# basisplatine.net
KiCad netlist of a schematic drawn in EAGLE
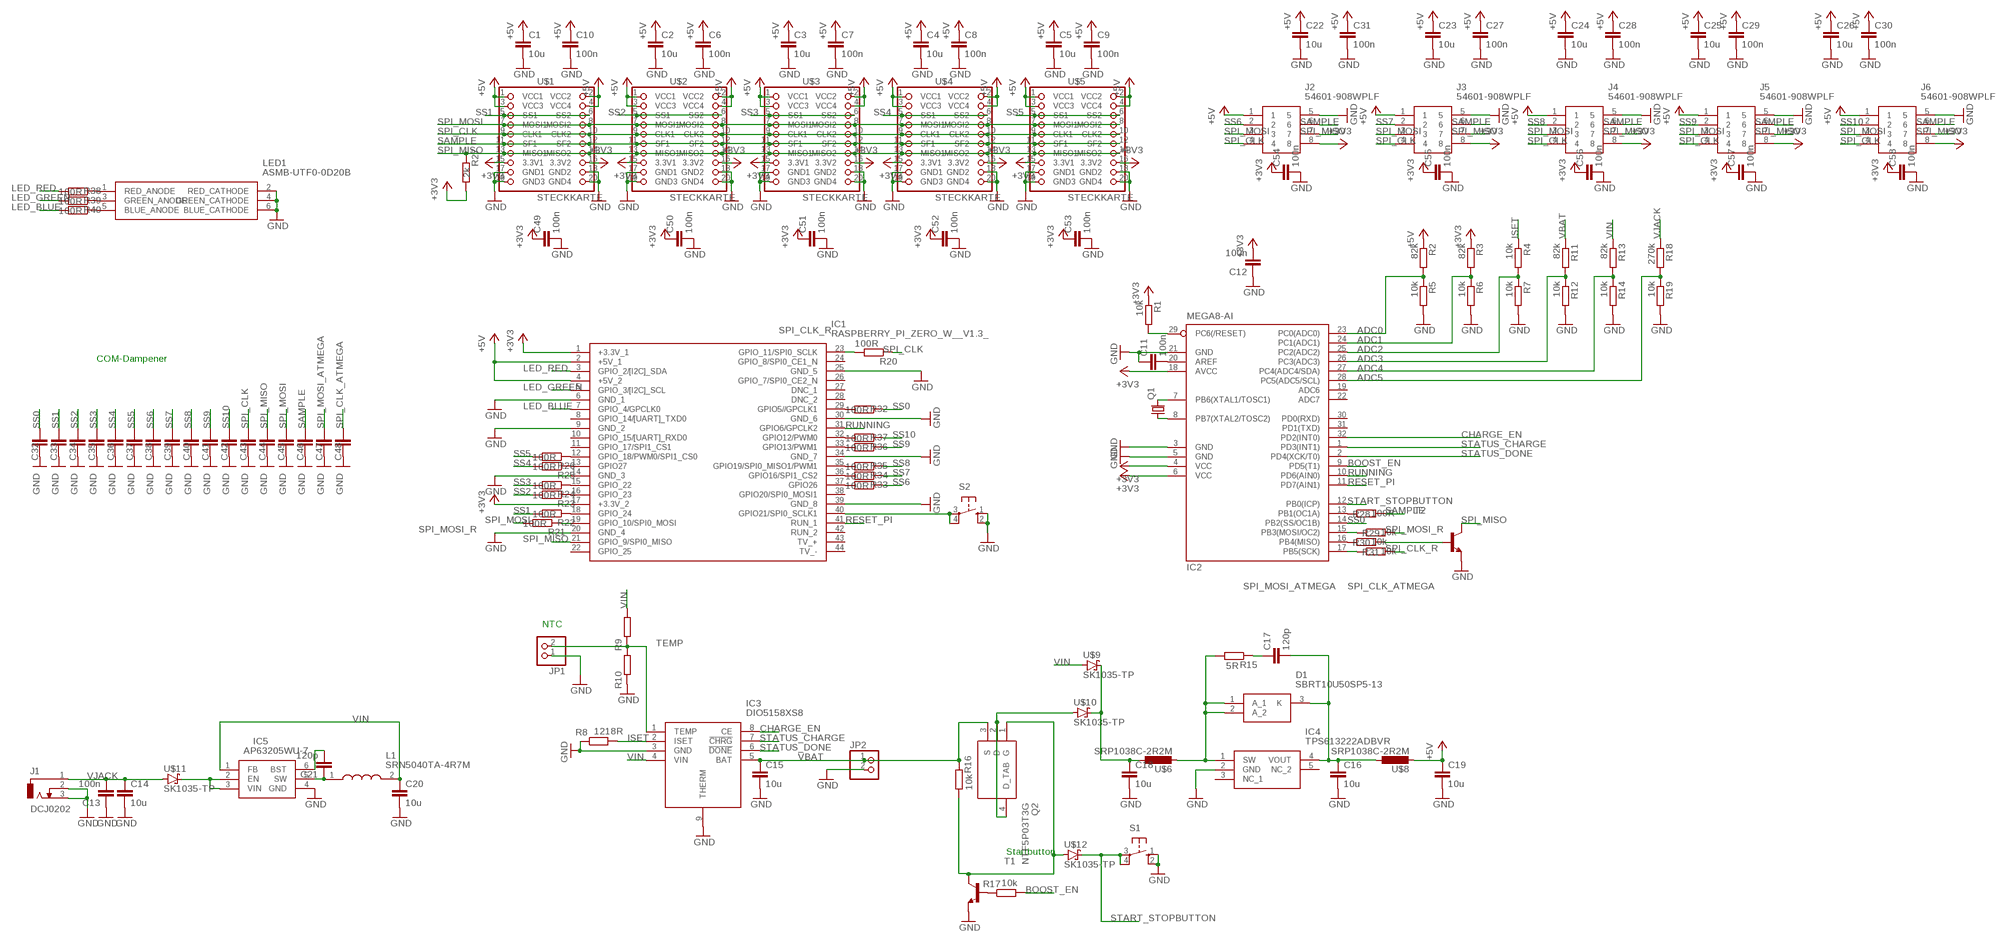
[diagram p0: schematic, sheet 1]

(export (version "E")
  (design (tool "Eeschema 10.0.6"))
  (components
    (comp (ref "C1")
      (value "10u")
      (footprint "eagle-import:C1206")
      (libsource (lib "eagle-import") (part "C-EUC1206"))
    )
    (comp (ref "C2")
      (value "10u")
      (footprint "eagle-import:C1206K")
      (libsource (lib "eagle-import") (part "C-EUC1206K"))
    )
    (comp (ref "C3")
      (value "10u")
      (footprint "eagle-import:C1206K")
      (libsource (lib "eagle-import") (part "C-EUC1206K"))
    )
    (comp (ref "C4")
      (value "10u")
      (footprint "eagle-import:C1206K")
      (libsource (lib "eagle-import") (part "C-EUC1206K"))
    )
    (comp (ref "C5")
      (value "10u")
      (footprint "eagle-import:C1206K")
      (libsource (lib "eagle-import") (part "C-EUC1206K"))
    )
    (comp (ref "C6")
      (value "100n")
      (footprint "eagle-import:C0603K")
      (libsource (lib "eagle-import") (part "C-EUC0603K"))
    )
    (comp (ref "C7")
      (value "100n")
      (footprint "eagle-import:C0603K")
      (libsource (lib "eagle-import") (part "C-EUC0603K"))
    )
    (comp (ref "C8")
      (value "100n")
      (footprint "eagle-import:C0603K")
      (libsource (lib "eagle-import") (part "C-EUC0603K"))
    )
    (comp (ref "C9")
      (value "100n")
      (footprint "eagle-import:C0603K")
      (libsource (lib "eagle-import") (part "C-EUC0603K"))
    )
    (comp (ref "C10")
      (value "100n")
      (footprint "eagle-import:C0603K")
      (libsource (lib "eagle-import") (part "C-EUC0603K"))
    )
    (comp (ref "C11")
      (value "100n")
      (footprint "eagle-import:C0603K")
      (libsource (lib "eagle-import") (part "C-EUC0603K"))
    )
    (comp (ref "C12")
      (value "100n")
      (footprint "eagle-import:C0603K")
      (libsource (lib "eagle-import") (part "C-EUC0603K"))
    )
    (comp (ref "C13")
      (value "100n")
      (footprint "eagle-import:C0603K")
      (libsource (lib "eagle-import") (part "C-EUC0603K"))
    )
    (comp (ref "C14")
      (value "10u")
      (footprint "eagle-import:C1206K")
      (libsource (lib "eagle-import") (part "C-EUC1206K"))
    )
    (comp (ref "C15")
      (value "10u")
      (footprint "eagle-import:C1206K")
      (libsource (lib "eagle-import") (part "C-EUC1206K"))
    )
    (comp (ref "C16")
      (value "10u")
      (footprint "eagle-import:C1206K")
      (libsource (lib "eagle-import") (part "C-EUC1206K"))
    )
    (comp (ref "C17")
      (value "120p")
      (footprint "eagle-import:C0603K")
      (libsource (lib "eagle-import") (part "C-EUC0603K"))
    )
    (comp (ref "C18")
      (value "10u")
      (footprint "eagle-import:C1206K")
      (libsource (lib "eagle-import") (part "C-EUC1206K"))
    )
    (comp (ref "C19")
      (value "10u")
      (footprint "eagle-import:C1206K")
      (libsource (lib "eagle-import") (part "C-EUC1206K"))
    )
    (comp (ref "C20")
      (value "10u")
      (footprint "eagle-import:C1206K")
      (libsource (lib "eagle-import") (part "C-EUC1206K"))
    )
    (comp (ref "C21")
      (value "120p")
      (footprint "eagle-import:C0603K")
      (libsource (lib "eagle-import") (part "C-EUC0603K"))
    )
    (comp (ref "C22")
      (value "10u")
      (footprint "eagle-import:C1206")
      (libsource (lib "eagle-import") (part "C-EUC1206"))
    )
    (comp (ref "C23")
      (value "10u")
      (footprint "eagle-import:C1206K")
      (libsource (lib "eagle-import") (part "C-EUC1206K"))
    )
    (comp (ref "C24")
      (value "10u")
      (footprint "eagle-import:C1206K")
      (libsource (lib "eagle-import") (part "C-EUC1206K"))
    )
    (comp (ref "C25")
      (value "10u")
      (footprint "eagle-import:C1206K")
      (libsource (lib "eagle-import") (part "C-EUC1206K"))
    )
    (comp (ref "C26")
      (value "10u")
      (footprint "eagle-import:C1206K")
      (libsource (lib "eagle-import") (part "C-EUC1206K"))
    )
    (comp (ref "C27")
      (value "100n")
      (footprint "eagle-import:C0603K")
      (libsource (lib "eagle-import") (part "C-EUC0603K"))
    )
    (comp (ref "C28")
      (value "100n")
      (footprint "eagle-import:C0603K")
      (libsource (lib "eagle-import") (part "C-EUC0603K"))
    )
    (comp (ref "C29")
      (value "100n")
      (footprint "eagle-import:C0603K")
      (libsource (lib "eagle-import") (part "C-EUC0603K"))
    )
    (comp (ref "C30")
      (value "100n")
      (footprint "eagle-import:C0603K")
      (libsource (lib "eagle-import") (part "C-EUC0603K"))
    )
    (comp (ref "C31")
      (value "100n")
      (footprint "eagle-import:C0603K")
      (libsource (lib "eagle-import") (part "C-EUC0603K"))
    )
    (comp (ref "C32")
      (value "C-EUC0603K")
      (footprint "eagle-import:C0603K")
      (libsource (lib "eagle-import") (part "C-EUC0603K"))
    )
    (comp (ref "C33")
      (value "C-EUC0603K")
      (footprint "eagle-import:C0603K")
      (libsource (lib "eagle-import") (part "C-EUC0603K"))
    )
    (comp (ref "C34")
      (value "C-EUC0603K")
      (footprint "eagle-import:C0603K")
      (libsource (lib "eagle-import") (part "C-EUC0603K"))
    )
    (comp (ref "C35")
      (value "C-EUC0603K")
      (footprint "eagle-import:C0603K")
      (libsource (lib "eagle-import") (part "C-EUC0603K"))
    )
    (comp (ref "C36")
      (value "C-EUC0603K")
      (footprint "eagle-import:C0603K")
      (libsource (lib "eagle-import") (part "C-EUC0603K"))
    )
    (comp (ref "C37")
      (value "C-EUC0603K")
      (footprint "eagle-import:C0603K")
      (libsource (lib "eagle-import") (part "C-EUC0603K"))
    )
    (comp (ref "C38")
      (value "C-EUC0603K")
      (footprint "eagle-import:C0603K")
      (libsource (lib "eagle-import") (part "C-EUC0603K"))
    )
    (comp (ref "C39")
      (value "C-EUC0603K")
      (footprint "eagle-import:C0603K")
      (libsource (lib "eagle-import") (part "C-EUC0603K"))
    )
    (comp (ref "C40")
      (value "C-EUC0603K")
      (footprint "eagle-import:C0603K")
      (libsource (lib "eagle-import") (part "C-EUC0603K"))
    )
    (comp (ref "C41")
      (value "C-EUC0603K")
      (footprint "eagle-import:C0603K")
      (libsource (lib "eagle-import") (part "C-EUC0603K"))
    )
    (comp (ref "C42")
      (value "C-EUC0603K")
      (footprint "eagle-import:C0603K")
      (libsource (lib "eagle-import") (part "C-EUC0603K"))
    )
    (comp (ref "C43")
      (value "C-EUC0603K")
      (footprint "eagle-import:C0603K")
      (libsource (lib "eagle-import") (part "C-EUC0603K"))
    )
    (comp (ref "C44")
      (value "C-EUC0603K")
      (footprint "eagle-import:C0603K")
      (libsource (lib "eagle-import") (part "C-EUC0603K"))
    )
    (comp (ref "C45")
      (value "C-EUC0603K")
      (footprint "eagle-import:C0603K")
      (libsource (lib "eagle-import") (part "C-EUC0603K"))
    )
    (comp (ref "C46")
      (value "C-EUC0603K")
      (footprint "eagle-import:C0603K")
      (libsource (lib "eagle-import") (part "C-EUC0603K"))
    )
    (comp (ref "C47")
      (value "C-EUC0603K")
      (footprint "eagle-import:C0603K")
      (libsource (lib "eagle-import") (part "C-EUC0603K"))
    )
    (comp (ref "C48")
      (value "C-EUC0603K")
      (footprint "eagle-import:C0603K")
      (libsource (lib "eagle-import") (part "C-EUC0603K"))
    )
    (comp (ref "C49")
      (value "100n")
      (footprint "eagle-import:C0603K")
      (libsource (lib "eagle-import") (part "C-EUC0603K"))
    )
    (comp (ref "C50")
      (value "100n")
      (footprint "eagle-import:C0603K")
      (libsource (lib "eagle-import") (part "C-EUC0603K"))
    )
    (comp (ref "C51")
      (value "100n")
      (footprint "eagle-import:C0603K")
      (libsource (lib "eagle-import") (part "C-EUC0603K"))
    )
    (comp (ref "C52")
      (value "100n")
      (footprint "eagle-import:C0603K")
      (libsource (lib "eagle-import") (part "C-EUC0603K"))
    )
    (comp (ref "C53")
      (value "100n")
      (footprint "eagle-import:C0603K")
      (libsource (lib "eagle-import") (part "C-EUC0603K"))
    )
    (comp (ref "C54")
      (value "100n")
      (footprint "eagle-import:C0603K")
      (libsource (lib "eagle-import") (part "C-EUC0603K"))
    )
    (comp (ref "C55")
      (value "100n")
      (footprint "eagle-import:C0603K")
      (libsource (lib "eagle-import") (part "C-EUC0603K"))
    )
    (comp (ref "C56")
      (value "100n")
      (footprint "eagle-import:C0603K")
      (libsource (lib "eagle-import") (part "C-EUC0603K"))
    )
    (comp (ref "C57")
      (value "100n")
      (footprint "eagle-import:C0603K")
      (libsource (lib "eagle-import") (part "C-EUC0603K"))
    )
    (comp (ref "C58")
      (value "100n")
      (footprint "eagle-import:C0603K")
      (libsource (lib "eagle-import") (part "C-EUC0603K"))
    )
    (comp (ref "D1")
      (value "SBRT10U50SP5-13")
      (footprint "eagle-import:SBRT10U50SP513")
      (fields (field (name "MOUSER_PART_NUMBER") "621-SBRT10U50SP5-13"))
      (libsource (lib "eagle-import") (part "SBRT10U50SP5-13"))
    )
    (comp (ref "IC1")
      (value "RASPBERRY_PI_ZERO_W__V1.3_")
      (footprint "eagle-import:RASPBERRYPIZEROWV13")
      (fields (field (name "MANUFACTURER_PART_NUMBER") "Raspberry Pi Zero W (v1.3)"))
      (libsource (lib "eagle-import") (part "RASPBERRY_PI_ZERO_W__V1.3_"))
    )
    (comp (ref "IC2")
      (value "MEGA8-AI")
      (footprint "eagle-import:TQFP32-08")
      (fields (field (name "MPN") "ATMEGA8-16AU"))
      (libsource (lib "eagle-import") (part "MEGA8-AI"))
    )
    (comp (ref "IC3")
      (value "DIO5158XS8")
      (footprint "eagle-import:SOIC127P600X170-9N")
      (fields (field (name "MOUSER_PART_NUMBER") "453-DIO5158XS8"))
      (libsource (lib "eagle-import") (part "DIO5158XS8"))
    )
    (comp (ref "IC4")
      (value "TPS613222ADBVR")
      (footprint "eagle-import:SOT95P280X145-5N")
      (fields (field (name "MOUSER_PART_NUMBER") "595-TPS613222ADBVR"))
      (libsource (lib "eagle-import") (part "TPS613222ADBVR"))
    )
    (comp (ref "IC5")
      (value "AP63205WU-7")
      (footprint "eagle-import:SOT95P280X100-6N")
      (fields (field (name "MOUSER_PART_NUMBER") "621-AP63205WU-7"))
      (libsource (lib "eagle-import") (part "AP63205WU-7"))
    )
    (comp (ref "J1")
      (value "DCJ0202")
      (footprint "eagle-import:DCJ0202")
      (libsource (lib "eagle-import") (part "DCJ0202"))
    )
    (comp (ref "J2")
      (value "54601-908WPLF")
      (footprint "eagle-import:54601908WPLF")
      (fields (field (name "MOUSER_PART_NUMBER") "649-54601-908WPLF"))
      (libsource (lib "eagle-import") (part "54601-908WPLF"))
    )
    (comp (ref "J3")
      (value "54601-908WPLF")
      (footprint "eagle-import:54601908WPLF")
      (fields (field (name "MOUSER_PART_NUMBER") "649-54601-908WPLF"))
      (libsource (lib "eagle-import") (part "54601-908WPLF"))
    )
    (comp (ref "J4")
      (value "54601-908WPLF")
      (footprint "eagle-import:54601908WPLF")
      (fields (field (name "MOUSER_PART_NUMBER") "649-54601-908WPLF"))
      (libsource (lib "eagle-import") (part "54601-908WPLF"))
    )
    (comp (ref "J5")
      (value "54601-908WPLF")
      (footprint "eagle-import:54601908WPLF")
      (fields (field (name "MOUSER_PART_NUMBER") "649-54601-908WPLF"))
      (libsource (lib "eagle-import") (part "54601-908WPLF"))
    )
    (comp (ref "J6")
      (value "54601-908WPLF")
      (footprint "eagle-import:54601908WPLF")
      (fields (field (name "MOUSER_PART_NUMBER") "649-54601-908WPLF"))
      (libsource (lib "eagle-import") (part "54601-908WPLF"))
    )
    (comp (ref "JP1")
      (value "PINHD-1X2")
      (footprint "eagle-import:1X02")
      (libsource (lib "eagle-import") (part "PINHD-1X2"))
    )
    (comp (ref "JP2")
      (value "PINHD-1X2")
      (footprint "eagle-import:1X02")
      (libsource (lib "eagle-import") (part "PINHD-1X2"))
    )
    (comp (ref "L1")
      (value "SRN5040TA-4R7M")
      (footprint "eagle-import:SRN5040TA4R7M")
      (fields (field (name "MOUSER_PART_NUMBER") "652-SRN5040TA-4R7M"))
      (libsource (lib "eagle-import") (part "SRN5040TA-4R7M"))
    )
    (comp (ref "LED1")
      (value "ASMB-UTF0-0D20B")
      (footprint "eagle-import:ASMBUTF00D20B")
      (fields (field (name "MOUSER_PART_NUMBER") "630-ASMB-UTF0-0D20B"))
      (libsource (lib "eagle-import") (part "ASMB-UTF0-0D20B"))
    )
    (comp (ref "Q1")
      (value "CRYSTALTC38H")
      (footprint "eagle-import:TC38H")
      (libsource (lib "eagle-import") (part "CRYSTALTC38H"))
    )
    (comp (ref "Q2")
      (value "NTF5P03T3G")
      (footprint "eagle-import:SOT230P700X175-4N")
      (fields (field (name "MOUSER_PART_NUMBER") "863-NTF5P03T3G"))
      (libsource (lib "eagle-import") (part "NTF5P03T3G"))
    )
    (comp (ref "R1")
      (value "10k")
      (footprint "eagle-import:R0603")
      (libsource (lib "eagle-import") (part "R-EU_R0603"))
    )
    (comp (ref "R2")
      (value "82k")
      (footprint "eagle-import:R0603")
      (libsource (lib "eagle-import") (part "R-EU_R0603"))
    )
    (comp (ref "R3")
      (value "82k")
      (footprint "eagle-import:R0603")
      (libsource (lib "eagle-import") (part "R-EU_R0603"))
    )
    (comp (ref "R4")
      (value "10k")
      (footprint "eagle-import:R0603")
      (libsource (lib "eagle-import") (part "R-EU_R0603"))
    )
    (comp (ref "R5")
      (value "10k")
      (footprint "eagle-import:R0603")
      (libsource (lib "eagle-import") (part "R-EU_R0603"))
    )
    (comp (ref "R6")
      (value "10k")
      (footprint "eagle-import:R0603")
      (libsource (lib "eagle-import") (part "R-EU_R0603"))
    )
    (comp (ref "R7")
      (value "10k")
      (footprint "eagle-import:R0603")
      (libsource (lib "eagle-import") (part "R-EU_R0603"))
    )
    (comp (ref "R8")
      (value "1218R")
      (footprint "eagle-import:R0603")
      (libsource (lib "eagle-import") (part "R-EU_R0603"))
    )
    (comp (ref "R9")
      (value "R-EU_R0603")
      (footprint "eagle-import:R0603")
      (libsource (lib "eagle-import") (part "R-EU_R0603"))
    )
    (comp (ref "R10")
      (value "R-EU_R0603")
      (footprint "eagle-import:R0603")
      (libsource (lib "eagle-import") (part "R-EU_R0603"))
    )
    (comp (ref "R11")
      (value "82k")
      (footprint "eagle-import:R0603")
      (libsource (lib "eagle-import") (part "R-EU_R0603"))
    )
    (comp (ref "R12")
      (value "10k")
      (footprint "eagle-import:R0603")
      (libsource (lib "eagle-import") (part "R-EU_R0603"))
    )
    (comp (ref "R13")
      (value "82k")
      (footprint "eagle-import:R0603")
      (libsource (lib "eagle-import") (part "R-EU_R0603"))
    )
    (comp (ref "R14")
      (value "10k")
      (footprint "eagle-import:R0603")
      (libsource (lib "eagle-import") (part "R-EU_R0603"))
    )
    (comp (ref "R15")
      (value "5R")
      (footprint "eagle-import:R0603")
      (libsource (lib "eagle-import") (part "R-EU_R0603"))
    )
    (comp (ref "R16")
      (value "10k")
      (footprint "eagle-import:R0603")
      (libsource (lib "eagle-import") (part "R-EU_R0603"))
    )
    (comp (ref "R17")
      (value "10k")
      (footprint "eagle-import:R0603")
      (libsource (lib "eagle-import") (part "R-EU_R0603"))
    )
    (comp (ref "R18")
      (value "270k")
      (footprint "eagle-import:R0603")
      (libsource (lib "eagle-import") (part "R-EU_R0603"))
    )
    (comp (ref "R19")
      (value "10k")
      (footprint "eagle-import:R0603")
      (libsource (lib "eagle-import") (part "R-EU_R0603"))
    )
    (comp (ref "R20")
      (value "100R")
      (footprint "eagle-import:R0603")
      (libsource (lib "eagle-import") (part "R-EU_R0603"))
    )
    (comp (ref "R21")
      (value "100R")
      (footprint "eagle-import:R0603")
      (libsource (lib "eagle-import") (part "R-EU_R0603"))
    )
    (comp (ref "R22")
      (value "100R")
      (footprint "eagle-import:R0603")
      (libsource (lib "eagle-import") (part "R-EU_R0603"))
    )
    (comp (ref "R23")
      (value "100R")
      (footprint "eagle-import:R0603")
      (libsource (lib "eagle-import") (part "R-EU_R0603"))
    )
    (comp (ref "R24")
      (value "100R")
      (footprint "eagle-import:R0603")
      (libsource (lib "eagle-import") (part "R-EU_R0603"))
    )
    (comp (ref "R25")
      (value "100R")
      (footprint "eagle-import:R0603")
      (libsource (lib "eagle-import") (part "R-EU_R0603"))
    )
    (comp (ref "R26")
      (value "100R")
      (footprint "eagle-import:R0603")
      (libsource (lib "eagle-import") (part "R-EU_R0603"))
    )
    (comp (ref "R27")
      (value "2k")
      (footprint "eagle-import:R0603")
      (libsource (lib "eagle-import") (part "R-EU_R0603"))
    )
    (comp (ref "R28")
      (value "100R")
      (footprint "eagle-import:R0603")
      (libsource (lib "eagle-import") (part "R-EU_R0603"))
    )
    (comp (ref "R29")
      (value "10k")
      (footprint "eagle-import:R0603")
      (libsource (lib "eagle-import") (part "R-EU_R0603"))
    )
    (comp (ref "R30")
      (value "10k")
      (footprint "eagle-import:R0603")
      (libsource (lib "eagle-import") (part "R-EU_R0603"))
    )
    (comp (ref "R31")
      (value "10k")
      (footprint "eagle-import:R0603")
      (libsource (lib "eagle-import") (part "R-EU_R0603"))
    )
    (comp (ref "R32")
      (value "100R")
      (footprint "eagle-import:R0603")
      (libsource (lib "eagle-import") (part "R-EU_R0603"))
    )
    (comp (ref "R33")
      (value "100R")
      (footprint "eagle-import:R0603")
      (libsource (lib "eagle-import") (part "R-EU_R0603"))
    )
    (comp (ref "R34")
      (value "100R")
      (footprint "eagle-import:R0603")
      (libsource (lib "eagle-import") (part "R-EU_R0603"))
    )
    (comp (ref "R35")
      (value "100R")
      (footprint "eagle-import:R0603")
      (libsource (lib "eagle-import") (part "R-EU_R0603"))
    )
    (comp (ref "R36")
      (value "100R")
      (footprint "eagle-import:R0603")
      (libsource (lib "eagle-import") (part "R-EU_R0603"))
    )
    (comp (ref "R37")
      (value "100R")
      (footprint "eagle-import:R0603")
      (libsource (lib "eagle-import") (part "R-EU_R0603"))
    )
    (comp (ref "R38")
      (value "100R")
      (footprint "eagle-import:R0603")
      (libsource (lib "eagle-import") (part "R-EU_R0603"))
    )
    (comp (ref "R39")
      (value "100R")
      (footprint "eagle-import:R0603")
      (libsource (lib "eagle-import") (part "R-EU_R0603"))
    )
    (comp (ref "R40")
      (value "100R")
      (footprint "eagle-import:R0603")
      (libsource (lib "eagle-import") (part "R-EU_R0603"))
    )
    (comp (ref "S1")
      (value "10-XX")
      (footprint "eagle-import:B3F-10XX")
      (fields (field (name "MPN") "B3F-1000"))
      (libsource (lib "eagle-import") (part "10-XX"))
    )
    (comp (ref "S2")
      (value "10-XX")
      (footprint "eagle-import:B3F-10XX")
      (fields (field (name "MPN") "B3F-1000"))
      (libsource (lib "eagle-import") (part "10-XX"))
    )
    (comp (ref "T1")
      (value "BC808-NPN-SOT23-BEC")
      (footprint "eagle-import:SOT23-BEC")
      (libsource (lib "eagle-import") (part "-NPN-SOT23-BECBC808"))
    )
    (comp (ref "T2")
      (value "BC808-NPN-SOT23-BEC")
      (footprint "eagle-import:SOT23-BEC")
      (libsource (lib "eagle-import") (part "-NPN-SOT23-BECBC808"))
    )
    (comp (ref "U$1")
      (value "STECKKARTE")
      (footprint "eagle-import:2X10")
      (libsource (lib "eagle-import") (part "STECKKARTE"))
    )
    (comp (ref "U$2")
      (value "STECKKARTE")
      (footprint "eagle-import:2X10")
      (libsource (lib "eagle-import") (part "STECKKARTE"))
    )
    (comp (ref "U$3")
      (value "STECKKARTE")
      (footprint "eagle-import:2X10")
      (libsource (lib "eagle-import") (part "STECKKARTE"))
    )
    (comp (ref "U$4")
      (value "STECKKARTE")
      (footprint "eagle-import:2X10")
      (libsource (lib "eagle-import") (part "STECKKARTE"))
    )
    (comp (ref "U$5")
      (value "STECKKARTE")
      (footprint "eagle-import:2X10")
      (libsource (lib "eagle-import") (part "STECKKARTE"))
    )
    (comp (ref "U$6")
      (value "SRP1038C-2R2M")
      (footprint "eagle-import:SRP1038C-2R2M")
      (libsource (lib "eagle-import") (part "SRP1038C-2R2M"))
    )
    (comp (ref "U$8")
      (value "SRP1038C-2R2M")
      (footprint "eagle-import:SRP1038C-2R2M")
      (libsource (lib "eagle-import") (part "SRP1038C-2R2M"))
    )
    (comp (ref "U$9")
      (value "SK1035-TP")
      (footprint "eagle-import:INDC2520X120N")
      (libsource (lib "eagle-import") (part "SK1035-TP"))
    )
    (comp (ref "U$10")
      (value "SK1035-TP")
      (footprint "eagle-import:INDC2520X120N")
      (libsource (lib "eagle-import") (part "SK1035-TP"))
    )
    (comp (ref "U$11")
      (value "SK1035-TP")
      (footprint "eagle-import:INDC2520X120N")
      (libsource (lib "eagle-import") (part "SK1035-TP"))
    )
    (comp (ref "U$12")
      (value "SK1035-TP")
      (footprint "eagle-import:INDC2520X120N")
      (libsource (lib "eagle-import") (part "SK1035-TP"))
    )
  )
  (nets
    (net (code "1") (name "+3V3") (class "Default")
      (node (ref "C12") (pin "2") (pinfunction "2_2") (pintype "passive"))
      (node (ref "C49") (pin "1") (pinfunction "1_1") (pintype "passive"))
      (node (ref "C50") (pin "1") (pinfunction "1_1") (pintype "passive"))
      (node (ref "C51") (pin "1") (pinfunction "1_1") (pintype "passive"))
      (node (ref "C52") (pin "1") (pinfunction "1_1") (pintype "passive"))
      (node (ref "C53") (pin "1") (pinfunction "1_1") (pintype "passive"))
      (node (ref "C54") (pin "1") (pinfunction "1_1") (pintype "passive"))
      (node (ref "C55") (pin "1") (pinfunction "1_1") (pintype "passive"))
      (node (ref "C56") (pin "1") (pinfunction "1_1") (pintype "passive"))
      (node (ref "C57") (pin "1") (pinfunction "1_1") (pintype "passive"))
      (node (ref "C58") (pin "1") (pinfunction "1_1") (pintype "passive"))
      (node (ref "IC1") (pin "1") (pinfunction "+3.3V_1_1") (pintype "bidirectional"))
      (node (ref "IC1") (pin "17") (pinfunction "+3.3V_2_17") (pintype "bidirectional"))
      (node (ref "IC2") (pin "18") (pinfunction "AVCC_18") (pintype "power_in"))
      (node (ref "IC2") (pin "4") (pinfunction "VCC_4") (pintype "power_in"))
      (node (ref "IC2") (pin "6") (pinfunction "VCC_6") (pintype "power_in"))
      (node (ref "J2") (pin "8") (pinfunction "8_8") (pintype "bidirectional"))
      (node (ref "J3") (pin "8") (pinfunction "8_8") (pintype "bidirectional"))
      (node (ref "J4") (pin "8") (pinfunction "8_8") (pintype "bidirectional"))
      (node (ref "J5") (pin "8") (pinfunction "8_8") (pintype "bidirectional"))
      (node (ref "J6") (pin "8") (pinfunction "8_8") (pintype "bidirectional"))
      (node (ref "R1") (pin "1") (pinfunction "1_1") (pintype "passive"))
      (node (ref "R27") (pin "2") (pinfunction "2_2") (pintype "passive"))
      (node (ref "R3") (pin "1") (pinfunction "1_1") (pintype "passive"))
      (node (ref "U$1") (pin "15") (pinfunction "3.3V1_15") (pintype "power_in"))
      (node (ref "U$1") (pin "16") (pinfunction "3.3V2_16") (pintype "power_in"))
      (node (ref "U$2") (pin "15") (pinfunction "3.3V1_15") (pintype "power_in"))
      (node (ref "U$2") (pin "16") (pinfunction "3.3V2_16") (pintype "power_in"))
      (node (ref "U$3") (pin "15") (pinfunction "3.3V1_15") (pintype "power_in"))
      (node (ref "U$3") (pin "16") (pinfunction "3.3V2_16") (pintype "power_in"))
      (node (ref "U$4") (pin "15") (pinfunction "3.3V1_15") (pintype "power_in"))
      (node (ref "U$4") (pin "16") (pinfunction "3.3V2_16") (pintype "power_in"))
      (node (ref "U$5") (pin "15") (pinfunction "3.3V1_15") (pintype "power_in"))
      (node (ref "U$5") (pin "16") (pinfunction "3.3V2_16") (pintype "power_in"))
    )
    (net (code "2") (name "+5V") (class "Default")
      (node (ref "C1") (pin "1") (pinfunction "1_1") (pintype "passive"))
      (node (ref "C10") (pin "1") (pinfunction "1_1") (pintype "passive"))
      (node (ref "C19") (pin "1") (pinfunction "1_1") (pintype "passive"))
      (node (ref "C2") (pin "1") (pinfunction "1_1") (pintype "passive"))
      (node (ref "C22") (pin "1") (pinfunction "1_1") (pintype "passive"))
      (node (ref "C23") (pin "1") (pinfunction "1_1") (pintype "passive"))
      (node (ref "C24") (pin "1") (pinfunction "1_1") (pintype "passive"))
      (node (ref "C25") (pin "1") (pinfunction "1_1") (pintype "passive"))
      (node (ref "C26") (pin "1") (pinfunction "1_1") (pintype "passive"))
      (node (ref "C27") (pin "1") (pinfunction "1_1") (pintype "passive"))
      (node (ref "C28") (pin "1") (pinfunction "1_1") (pintype "passive"))
      (node (ref "C29") (pin "1") (pinfunction "1_1") (pintype "passive"))
      (node (ref "C3") (pin "1") (pinfunction "1_1") (pintype "passive"))
      (node (ref "C30") (pin "1") (pinfunction "1_1") (pintype "passive"))
      (node (ref "C31") (pin "1") (pinfunction "1_1") (pintype "passive"))
      (node (ref "C4") (pin "1") (pinfunction "1_1") (pintype "passive"))
      (node (ref "C5") (pin "1") (pinfunction "1_1") (pintype "passive"))
      (node (ref "C6") (pin "1") (pinfunction "1_1") (pintype "passive"))
      (node (ref "C7") (pin "1") (pinfunction "1_1") (pintype "passive"))
      (node (ref "C8") (pin "1") (pinfunction "1_1") (pintype "passive"))
      (node (ref "C9") (pin "1") (pinfunction "1_1") (pintype "passive"))
      (node (ref "IC1") (pin "2") (pinfunction "+5V_1_2") (pintype "bidirectional"))
      (node (ref "IC1") (pin "4") (pinfunction "+5V_2_4") (pintype "bidirectional"))
      (node (ref "J2") (pin "1") (pinfunction "1_1") (pintype "bidirectional"))
      (node (ref "J3") (pin "1") (pinfunction "1_1") (pintype "bidirectional"))
      (node (ref "J4") (pin "1") (pinfunction "1_1") (pintype "bidirectional"))
      (node (ref "J5") (pin "1") (pinfunction "1_1") (pintype "bidirectional"))
      (node (ref "J6") (pin "1") (pinfunction "1_1") (pintype "bidirectional"))
      (node (ref "R2") (pin "1") (pinfunction "1_1") (pintype "passive"))
      (node (ref "U$1") (pin "1") (pinfunction "VCC1_1") (pintype "power_in"))
      (node (ref "U$1") (pin "2") (pinfunction "VCC2_2") (pintype "power_in"))
      (node (ref "U$1") (pin "3") (pinfunction "VCC3_3") (pintype "power_in"))
      (node (ref "U$1") (pin "4") (pinfunction "VCC4_4") (pintype "power_in"))
      (node (ref "U$2") (pin "1") (pinfunction "VCC1_1") (pintype "power_in"))
      (node (ref "U$2") (pin "2") (pinfunction "VCC2_2") (pintype "power_in"))
      (node (ref "U$2") (pin "3") (pinfunction "VCC3_3") (pintype "power_in"))
      (node (ref "U$2") (pin "4") (pinfunction "VCC4_4") (pintype "power_in"))
      (node (ref "U$3") (pin "1") (pinfunction "VCC1_1") (pintype "power_in"))
      (node (ref "U$3") (pin "2") (pinfunction "VCC2_2") (pintype "power_in"))
      (node (ref "U$3") (pin "3") (pinfunction "VCC3_3") (pintype "power_in"))
      (node (ref "U$3") (pin "4") (pinfunction "VCC4_4") (pintype "power_in"))
      (node (ref "U$4") (pin "1") (pinfunction "VCC1_1") (pintype "power_in"))
      (node (ref "U$4") (pin "2") (pinfunction "VCC2_2") (pintype "power_in"))
      (node (ref "U$4") (pin "3") (pinfunction "VCC3_3") (pintype "power_in"))
      (node (ref "U$4") (pin "4") (pinfunction "VCC4_4") (pintype "power_in"))
      (node (ref "U$5") (pin "1") (pinfunction "VCC1_1") (pintype "power_in"))
      (node (ref "U$5") (pin "2") (pinfunction "VCC2_2") (pintype "power_in"))
      (node (ref "U$5") (pin "3") (pinfunction "VCC3_3") (pintype "power_in"))
      (node (ref "U$5") (pin "4") (pinfunction "VCC4_4") (pintype "power_in"))
      (node (ref "U$8") (pin "P$2") (pinfunction "2_P$2") (pintype "passive"))
    )
    (net (code "3") (name "/ADC0") (class "Default")
      (node (ref "IC2") (pin "23") (pinfunction "PC0(ADC0)_23") (pintype "bidirectional"))
      (node (ref "R2") (pin "2") (pinfunction "2_2") (pintype "passive"))
      (node (ref "R5") (pin "1") (pinfunction "1_1") (pintype "passive"))
    )
    (net (code "4") (name "/ADC1") (class "Default")
      (node (ref "IC2") (pin "24") (pinfunction "PC1(ADC1)_24") (pintype "bidirectional"))
      (node (ref "R3") (pin "2") (pinfunction "2_2") (pintype "passive"))
      (node (ref "R6") (pin "1") (pinfunction "1_1") (pintype "passive"))
    )
    (net (code "5") (name "/ADC2") (class "Default")
      (node (ref "IC2") (pin "25") (pinfunction "PC2(ADC2)_25") (pintype "bidirectional"))
      (node (ref "R4") (pin "2") (pinfunction "2_2") (pintype "passive"))
      (node (ref "R7") (pin "1") (pinfunction "1_1") (pintype "passive"))
    )
    (net (code "6") (name "/ADC3") (class "Default")
      (node (ref "IC2") (pin "26") (pinfunction "PC3(ADC3)_26") (pintype "bidirectional"))
      (node (ref "R11") (pin "2") (pinfunction "2_2") (pintype "passive"))
      (node (ref "R12") (pin "1") (pinfunction "1_1") (pintype "passive"))
    )
    (net (code "7") (name "/ADC4") (class "Default")
      (node (ref "IC2") (pin "27") (pinfunction "PC4(ADC4/SDA)_27") (pintype "bidirectional"))
      (node (ref "R13") (pin "2") (pinfunction "2_2") (pintype "passive"))
      (node (ref "R14") (pin "1") (pinfunction "1_1") (pintype "passive"))
    )
    (net (code "8") (name "/ADC5") (class "Default")
      (node (ref "IC2") (pin "28") (pinfunction "PC5(ADC5/SCL)_28") (pintype "bidirectional"))
      (node (ref "R18") (pin "2") (pinfunction "2_2") (pintype "passive"))
      (node (ref "R19") (pin "1") (pinfunction "1_1") (pintype "passive"))
    )
    (net (code "9") (name "/BOOST_EN") (class "Default")
      (node (ref "IC2") (pin "9") (pinfunction "PD5(T1)_9") (pintype "bidirectional"))
      (node (ref "R17") (pin "2") (pinfunction "2_2") (pintype "passive"))
    )
    (net (code "10") (name "/CHARGE_EN") (class "Default")
      (node (ref "IC2") (pin "32") (pinfunction "PD2(INT0)_32") (pintype "bidirectional"))
      (node (ref "IC3") (pin "8") (pinfunction "CE_8") (pintype "input"))
    )
    (net (code "11") (name "/ISET") (class "Default")
      (node (ref "IC3") (pin "2") (pinfunction "ISET_2") (pintype "bidirectional"))
      (node (ref "R4") (pin "1") (pinfunction "1_1") (pintype "passive"))
      (node (ref "R8") (pin "2") (pinfunction "2_2") (pintype "passive"))
    )
    (net (code "12") (name "/LED_BLUE") (class "Default")
      (node (ref "IC1") (pin "7") (pinfunction "GPIO_4/GPCLK0_7") (pintype "bidirectional"))
      (node (ref "R40") (pin "2") (pinfunction "2_2") (pintype "passive"))
    )
    (net (code "13") (name "/LED_GREEN") (class "Default")
      (node (ref "IC1") (pin "5") (pinfunction "GPIO_3/[I2C]_SCL_5") (pintype "bidirectional"))
      (node (ref "R39") (pin "2") (pinfunction "2_2") (pintype "passive"))
    )
    (net (code "14") (name "/LED_RED") (class "Default")
      (node (ref "IC1") (pin "3") (pinfunction "GPIO_2/[I2C]_SDA_3") (pintype "bidirectional"))
      (node (ref "R38") (pin "2") (pinfunction "2_2") (pintype "passive"))
    )
    (net (code "15") (name "/RESET_PI") (class "Default")
      (node (ref "IC1") (pin "41") (pinfunction "RUN_1_41") (pintype "bidirectional"))
      (node (ref "IC2") (pin "11") (pinfunction "PD7(AIN1)_11") (pintype "bidirectional"))
    )
    (net (code "16") (name "/RUNNING") (class "Default")
      (node (ref "IC1") (pin "31") (pinfunction "GPIO6/GPCLK2_31") (pintype "bidirectional"))
      (node (ref "IC2") (pin "10") (pinfunction "PD6(AIN0)_10") (pintype "bidirectional"))
    )
    (net (code "17") (name "/SAMPLE") (class "Default")
      (node (ref "C46") (pin "2") (pinfunction "2_2") (pintype "passive"))
      (node (ref "J2") (pin "6") (pinfunction "6_6") (pintype "bidirectional"))
      (node (ref "J3") (pin "6") (pinfunction "6_6") (pintype "bidirectional"))
      (node (ref "J4") (pin "6") (pinfunction "6_6") (pintype "bidirectional"))
      (node (ref "J5") (pin "6") (pinfunction "6_6") (pintype "bidirectional"))
      (node (ref "J6") (pin "6") (pinfunction "6_6") (pintype "bidirectional"))
      (node (ref "R28") (pin "2") (pinfunction "2_2") (pintype "passive"))
      (node (ref "U$1") (pin "11") (pinfunction "SF1_11") (pintype "input"))
      (node (ref "U$1") (pin "12") (pinfunction "SF2_12") (pintype "input"))
      (node (ref "U$2") (pin "11") (pinfunction "SF1_11") (pintype "input"))
      (node (ref "U$2") (pin "12") (pinfunction "SF2_12") (pintype "input"))
      (node (ref "U$3") (pin "11") (pinfunction "SF1_11") (pintype "input"))
      (node (ref "U$3") (pin "12") (pinfunction "SF2_12") (pintype "input"))
      (node (ref "U$4") (pin "11") (pinfunction "SF1_11") (pintype "input"))
      (node (ref "U$4") (pin "12") (pinfunction "SF2_12") (pintype "input"))
      (node (ref "U$5") (pin "11") (pinfunction "SF1_11") (pintype "input"))
      (node (ref "U$5") (pin "12") (pinfunction "SF2_12") (pintype "input"))
    )
    (net (code "18") (name "/SPI_CLK") (class "Default")
      (node (ref "C43") (pin "2") (pinfunction "2_2") (pintype "passive"))
      (node (ref "J2") (pin "4") (pinfunction "4_4") (pintype "bidirectional"))
      (node (ref "J3") (pin "4") (pinfunction "4_4") (pintype "bidirectional"))
      (node (ref "J4") (pin "4") (pinfunction "4_4") (pintype "bidirectional"))
      (node (ref "J5") (pin "4") (pinfunction "4_4") (pintype "bidirectional"))
      (node (ref "J6") (pin "4") (pinfunction "4_4") (pintype "bidirectional"))
      (node (ref "R20") (pin "1") (pinfunction "1_1") (pintype "passive"))
      (node (ref "U$1") (pin "10") (pinfunction "CLK2_10") (pintype "input"))
      (node (ref "U$1") (pin "9") (pinfunction "CLK1_9") (pintype "input"))
      (node (ref "U$2") (pin "10") (pinfunction "CLK2_10") (pintype "input"))
      (node (ref "U$2") (pin "9") (pinfunction "CLK1_9") (pintype "input"))
      (node (ref "U$3") (pin "10") (pinfunction "CLK2_10") (pintype "input"))
      (node (ref "U$3") (pin "9") (pinfunction "CLK1_9") (pintype "input"))
      (node (ref "U$4") (pin "10") (pinfunction "CLK2_10") (pintype "input"))
      (node (ref "U$4") (pin "9") (pinfunction "CLK1_9") (pintype "input"))
      (node (ref "U$5") (pin "10") (pinfunction "CLK2_10") (pintype "input"))
      (node (ref "U$5") (pin "9") (pinfunction "CLK1_9") (pintype "input"))
    )
    (net (code "19") (name "/SPI_CLK_ATMEGA") (class "Default")
      (node (ref "C48") (pin "2") (pinfunction "2_2") (pintype "passive"))
      (node (ref "IC2") (pin "17") (pinfunction "PB5(SCK)_17") (pintype "bidirectional"))
      (node (ref "R31") (pin "1") (pinfunction "1_1") (pintype "passive"))
    )
    (net (code "20") (name "/SPI_CLK_R") (class "Default")
      (node (ref "IC1") (pin "23") (pinfunction "GPIO_11/SPI0_SCLK_23") (pintype "bidirectional"))
      (node (ref "R20") (pin "2") (pinfunction "2_2") (pintype "passive"))
      (node (ref "R31") (pin "2") (pinfunction "2_2") (pintype "passive"))
    )
    (net (code "21") (name "/SPI_MISO") (class "Default")
      (node (ref "C44") (pin "2") (pinfunction "2_2") (pintype "passive"))
      (node (ref "IC1") (pin "21") (pinfunction "GPIO_9/SPI0_MISO_21") (pintype "bidirectional"))
      (node (ref "J2") (pin "7") (pinfunction "7_7") (pintype "bidirectional"))
      (node (ref "J3") (pin "7") (pinfunction "7_7") (pintype "bidirectional"))
      (node (ref "J4") (pin "7") (pinfunction "7_7") (pintype "bidirectional"))
      (node (ref "J5") (pin "7") (pinfunction "7_7") (pintype "bidirectional"))
      (node (ref "J6") (pin "7") (pinfunction "7_7") (pintype "bidirectional"))
      (node (ref "R27") (pin "1") (pinfunction "1_1") (pintype "passive"))
      (node (ref "T2") (pin "C") (pinfunction "C_C") (pintype "passive"))
      (node (ref "U$1") (pin "13") (pinfunction "MISO1_13") (pintype "output"))
      (node (ref "U$1") (pin "14") (pinfunction "MISO2_14") (pintype "output"))
      (node (ref "U$2") (pin "13") (pinfunction "MISO1_13") (pintype "output"))
      (node (ref "U$2") (pin "14") (pinfunction "MISO2_14") (pintype "output"))
      (node (ref "U$3") (pin "13") (pinfunction "MISO1_13") (pintype "output"))
      (node (ref "U$3") (pin "14") (pinfunction "MISO2_14") (pintype "output"))
      (node (ref "U$4") (pin "13") (pinfunction "MISO1_13") (pintype "output"))
      (node (ref "U$4") (pin "14") (pinfunction "MISO2_14") (pintype "output"))
      (node (ref "U$5") (pin "13") (pinfunction "MISO1_13") (pintype "output"))
      (node (ref "U$5") (pin "14") (pinfunction "MISO2_14") (pintype "output"))
    )
    (net (code "22") (name "/SPI_MOSI") (class "Default")
      (node (ref "C45") (pin "2") (pinfunction "2_2") (pintype "passive"))
      (node (ref "J2") (pin "3") (pinfunction "3_3") (pintype "bidirectional"))
      (node (ref "J3") (pin "3") (pinfunction "3_3") (pintype "bidirectional"))
      (node (ref "J4") (pin "3") (pinfunction "3_3") (pintype "bidirectional"))
      (node (ref "J5") (pin "3") (pinfunction "3_3") (pintype "bidirectional"))
      (node (ref "J6") (pin "3") (pinfunction "3_3") (pintype "bidirectional"))
      (node (ref "R21") (pin "2") (pinfunction "2_2") (pintype "passive"))
      (node (ref "U$1") (pin "7") (pinfunction "MOSI1_7") (pintype "input"))
      (node (ref "U$1") (pin "8") (pinfunction "MOSI2_8") (pintype "input"))
      (node (ref "U$2") (pin "7") (pinfunction "MOSI1_7") (pintype "input"))
      (node (ref "U$2") (pin "8") (pinfunction "MOSI2_8") (pintype "input"))
      (node (ref "U$3") (pin "7") (pinfunction "MOSI1_7") (pintype "input"))
      (node (ref "U$3") (pin "8") (pinfunction "MOSI2_8") (pintype "input"))
      (node (ref "U$4") (pin "7") (pinfunction "MOSI1_7") (pintype "input"))
      (node (ref "U$4") (pin "8") (pinfunction "MOSI2_8") (pintype "input"))
      (node (ref "U$5") (pin "7") (pinfunction "MOSI1_7") (pintype "input"))
      (node (ref "U$5") (pin "8") (pinfunction "MOSI2_8") (pintype "input"))
    )
    (net (code "23") (name "/SPI_MOSI_ATMEGA") (class "Default")
      (node (ref "C47") (pin "2") (pinfunction "2_2") (pintype "passive"))
      (node (ref "IC2") (pin "15") (pinfunction "PB3(MOSI/OC2)_15") (pintype "bidirectional"))
      (node (ref "R29") (pin "1") (pinfunction "1_1") (pintype "passive"))
    )
    (net (code "24") (name "/SPI_MOSI_R") (class "Default")
      (node (ref "IC1") (pin "19") (pinfunction "GPIO_10/SPI0_MOSI_19") (pintype "bidirectional"))
      (node (ref "R21") (pin "1") (pinfunction "1_1") (pintype "passive"))
      (node (ref "R29") (pin "2") (pinfunction "2_2") (pintype "passive"))
    )
    (net (code "25") (name "/SS0") (class "Default")
      (node (ref "C32") (pin "2") (pinfunction "2_2") (pintype "passive"))
      (node (ref "IC2") (pin "14") (pinfunction "PB2(SS/OC1B)_14") (pintype "bidirectional"))
      (node (ref "R32") (pin "1") (pinfunction "1_1") (pintype "passive"))
    )
    (net (code "26") (name "/SS1") (class "Default")
      (node (ref "C33") (pin "2") (pinfunction "2_2") (pintype "passive"))
      (node (ref "R22") (pin "2") (pinfunction "2_2") (pintype "passive"))
      (node (ref "U$1") (pin "5") (pinfunction "SS1_5") (pintype "input"))
      (node (ref "U$1") (pin "6") (pinfunction "SS2_6") (pintype "input"))
    )
    (net (code "27") (name "/SS2") (class "Default")
      (node (ref "C34") (pin "2") (pinfunction "2_2") (pintype "passive"))
      (node (ref "R23") (pin "2") (pinfunction "2_2") (pintype "passive"))
      (node (ref "U$2") (pin "5") (pinfunction "SS1_5") (pintype "input"))
      (node (ref "U$2") (pin "6") (pinfunction "SS2_6") (pintype "input"))
    )
    (net (code "28") (name "/SS3") (class "Default")
      (node (ref "C35") (pin "2") (pinfunction "2_2") (pintype "passive"))
      (node (ref "R24") (pin "2") (pinfunction "2_2") (pintype "passive"))
      (node (ref "U$3") (pin "5") (pinfunction "SS1_5") (pintype "input"))
      (node (ref "U$3") (pin "6") (pinfunction "SS2_6") (pintype "input"))
    )
    (net (code "29") (name "/SS4") (class "Default")
      (node (ref "C36") (pin "2") (pinfunction "2_2") (pintype "passive"))
      (node (ref "R25") (pin "2") (pinfunction "2_2") (pintype "passive"))
      (node (ref "U$4") (pin "5") (pinfunction "SS1_5") (pintype "input"))
      (node (ref "U$4") (pin "6") (pinfunction "SS2_6") (pintype "input"))
    )
    (net (code "30") (name "/SS5") (class "Default")
      (node (ref "C37") (pin "2") (pinfunction "2_2") (pintype "passive"))
      (node (ref "R26") (pin "2") (pinfunction "2_2") (pintype "passive"))
      (node (ref "U$5") (pin "5") (pinfunction "SS1_5") (pintype "input"))
      (node (ref "U$5") (pin "6") (pinfunction "SS2_6") (pintype "input"))
    )
    (net (code "31") (name "/SS6") (class "Default")
      (node (ref "C38") (pin "2") (pinfunction "2_2") (pintype "passive"))
      (node (ref "J2") (pin "2") (pinfunction "2_2") (pintype "bidirectional"))
      (node (ref "R33") (pin "1") (pinfunction "1_1") (pintype "passive"))
    )
    (net (code "32") (name "/SS7") (class "Default")
      (node (ref "C39") (pin "2") (pinfunction "2_2") (pintype "passive"))
      (node (ref "J3") (pin "2") (pinfunction "2_2") (pintype "bidirectional"))
      (node (ref "R34") (pin "1") (pinfunction "1_1") (pintype "passive"))
    )
    (net (code "33") (name "/SS8") (class "Default")
      (node (ref "C40") (pin "2") (pinfunction "2_2") (pintype "passive"))
      (node (ref "J4") (pin "2") (pinfunction "2_2") (pintype "bidirectional"))
      (node (ref "R35") (pin "1") (pinfunction "1_1") (pintype "passive"))
    )
    (net (code "34") (name "/SS9") (class "Default")
      (node (ref "C41") (pin "2") (pinfunction "2_2") (pintype "passive"))
      (node (ref "J5") (pin "2") (pinfunction "2_2") (pintype "bidirectional"))
      (node (ref "R36") (pin "1") (pinfunction "1_1") (pintype "passive"))
    )
    (net (code "35") (name "/SS10") (class "Default")
      (node (ref "C42") (pin "2") (pinfunction "2_2") (pintype "passive"))
      (node (ref "J6") (pin "2") (pinfunction "2_2") (pintype "bidirectional"))
      (node (ref "R37") (pin "1") (pinfunction "1_1") (pintype "passive"))
    )
    (net (code "36") (name "/START_STOPBUTTON") (class "Default")
      (node (ref "IC2") (pin "12") (pinfunction "PB0(ICP)_12") (pintype "bidirectional"))
      (node (ref "S1") (pin "3") (pinfunction "P_3") (pintype "passive"))
      (node (ref "S1") (pin "4") (pinfunction "P1_4") (pintype "passive"))
      (node (ref "U$12") (pin "2") (pinfunction "C_2") (pintype "passive"))
    )
    (net (code "37") (name "/STATUS_CHARGE") (class "Default")
      (node (ref "IC2") (pin "1") (pinfunction "PD3(INT1)_1") (pintype "bidirectional"))
      (node (ref "IC3") (pin "7") (pinfunction "~{CHRG}_7") (pintype "output"))
    )
    (net (code "38") (name "/STATUS_DONE") (class "Default")
      (node (ref "IC2") (pin "2") (pinfunction "PD4(XCK/T0)_2") (pintype "bidirectional"))
      (node (ref "IC3") (pin "6") (pinfunction "~{DONE}_6") (pintype "output"))
    )
    (net (code "39") (name "/TEMP") (class "Default")
      (node (ref "IC3") (pin "1") (pinfunction "TEMP_1") (pintype "input"))
      (node (ref "JP1") (pin "2") (pinfunction "2_2") (pintype "passive"))
      (node (ref "R10") (pin "2") (pinfunction "2_2") (pintype "passive"))
      (node (ref "R9") (pin "1") (pinfunction "1_1") (pintype "passive"))
    )
    (net (code "40") (name "/VBAT") (class "Default")
      (node (ref "C15") (pin "1") (pinfunction "1_1") (pintype "passive"))
      (node (ref "IC3") (pin "5") (pinfunction "BAT_5") (pintype "power_in"))
      (node (ref "JP2") (pin "1") (pinfunction "1_1") (pintype "passive"))
      (node (ref "Q2") (pin "3") (pinfunction "S_3") (pintype "bidirectional"))
      (node (ref "R11") (pin "1") (pinfunction "1_1") (pintype "passive"))
      (node (ref "R16") (pin "1") (pinfunction "1_1") (pintype "passive"))
    )
    (net (code "41") (name "/VIN") (class "Default")
      (node (ref "C20") (pin "1") (pinfunction "1_1") (pintype "passive"))
      (node (ref "IC3") (pin "4") (pinfunction "VIN_4") (pintype "power_in"))
      (node (ref "IC5") (pin "1") (pinfunction "FB_1") (pintype "bidirectional"))
      (node (ref "L1") (pin "2") (pinfunction "2_2") (pintype "bidirectional"))
      (node (ref "R13") (pin "1") (pinfunction "1_1") (pintype "passive"))
      (node (ref "R9") (pin "2") (pinfunction "2_2") (pintype "passive"))
      (node (ref "U$9") (pin "1") (pinfunction "A_1") (pintype "passive"))
    )
    (net (code "42") (name "/VJACK") (class "Default")
      (node (ref "C13") (pin "2") (pinfunction "2_2") (pintype "passive"))
      (node (ref "C14") (pin "1") (pinfunction "1_1") (pintype "passive"))
      (node (ref "J1") (pin "1") (pinfunction "1_1") (pintype "passive"))
      (node (ref "R18") (pin "1") (pinfunction "1_1") (pintype "passive"))
      (node (ref "U$11") (pin "1") (pinfunction "A_1") (pintype "passive"))
    )
    (net (code "43") (name "GND") (class "Default")
      (node (ref "C1") (pin "2") (pinfunction "2_2") (pintype "passive"))
      (node (ref "C10") (pin "2") (pinfunction "2_2") (pintype "passive"))
      (node (ref "C11") (pin "1") (pinfunction "1_1") (pintype "passive"))
      (node (ref "C12") (pin "1") (pinfunction "1_1") (pintype "passive"))
      (node (ref "C13") (pin "1") (pinfunction "1_1") (pintype "passive"))
      (node (ref "C14") (pin "2") (pinfunction "2_2") (pintype "passive"))
      (node (ref "C15") (pin "2") (pinfunction "2_2") (pintype "passive"))
      (node (ref "C16") (pin "2") (pinfunction "2_2") (pintype "passive"))
      (node (ref "C18") (pin "2") (pinfunction "2_2") (pintype "passive"))
      (node (ref "C19") (pin "2") (pinfunction "2_2") (pintype "passive"))
      (node (ref "C2") (pin "2") (pinfunction "2_2") (pintype "passive"))
      (node (ref "C20") (pin "2") (pinfunction "2_2") (pintype "passive"))
      (node (ref "C22") (pin "2") (pinfunction "2_2") (pintype "passive"))
      (node (ref "C23") (pin "2") (pinfunction "2_2") (pintype "passive"))
      (node (ref "C24") (pin "2") (pinfunction "2_2") (pintype "passive"))
      (node (ref "C25") (pin "2") (pinfunction "2_2") (pintype "passive"))
      (node (ref "C26") (pin "2") (pinfunction "2_2") (pintype "passive"))
      (node (ref "C27") (pin "2") (pinfunction "2_2") (pintype "passive"))
      (node (ref "C28") (pin "2") (pinfunction "2_2") (pintype "passive"))
      (node (ref "C29") (pin "2") (pinfunction "2_2") (pintype "passive"))
      (node (ref "C3") (pin "2") (pinfunction "2_2") (pintype "passive"))
      (node (ref "C30") (pin "2") (pinfunction "2_2") (pintype "passive"))
      (node (ref "C31") (pin "2") (pinfunction "2_2") (pintype "passive"))
      (node (ref "C32") (pin "1") (pinfunction "1_1") (pintype "passive"))
      (node (ref "C33") (pin "1") (pinfunction "1_1") (pintype "passive"))
      (node (ref "C34") (pin "1") (pinfunction "1_1") (pintype "passive"))
      (node (ref "C35") (pin "1") (pinfunction "1_1") (pintype "passive"))
      (node (ref "C36") (pin "1") (pinfunction "1_1") (pintype "passive"))
      (node (ref "C37") (pin "1") (pinfunction "1_1") (pintype "passive"))
      (node (ref "C38") (pin "1") (pinfunction "1_1") (pintype "passive"))
      (node (ref "C39") (pin "1") (pinfunction "1_1") (pintype "passive"))
      (node (ref "C4") (pin "2") (pinfunction "2_2") (pintype "passive"))
      (node (ref "C40") (pin "1") (pinfunction "1_1") (pintype "passive"))
      (node (ref "C41") (pin "1") (pinfunction "1_1") (pintype "passive"))
      (node (ref "C42") (pin "1") (pinfunction "1_1") (pintype "passive"))
      (node (ref "C43") (pin "1") (pinfunction "1_1") (pintype "passive"))
      (node (ref "C44") (pin "1") (pinfunction "1_1") (pintype "passive"))
      (node (ref "C45") (pin "1") (pinfunction "1_1") (pintype "passive"))
      (node (ref "C46") (pin "1") (pinfunction "1_1") (pintype "passive"))
      (node (ref "C47") (pin "1") (pinfunction "1_1") (pintype "passive"))
      (node (ref "C48") (pin "1") (pinfunction "1_1") (pintype "passive"))
      (node (ref "C49") (pin "2") (pinfunction "2_2") (pintype "passive"))
      (node (ref "C5") (pin "2") (pinfunction "2_2") (pintype "passive"))
      (node (ref "C50") (pin "2") (pinfunction "2_2") (pintype "passive"))
      (node (ref "C51") (pin "2") (pinfunction "2_2") (pintype "passive"))
      (node (ref "C52") (pin "2") (pinfunction "2_2") (pintype "passive"))
      (node (ref "C53") (pin "2") (pinfunction "2_2") (pintype "passive"))
      (node (ref "C54") (pin "2") (pinfunction "2_2") (pintype "passive"))
      (node (ref "C55") (pin "2") (pinfunction "2_2") (pintype "passive"))
      (node (ref "C56") (pin "2") (pinfunction "2_2") (pintype "passive"))
      (node (ref "C57") (pin "2") (pinfunction "2_2") (pintype "passive"))
      (node (ref "C58") (pin "2") (pinfunction "2_2") (pintype "passive"))
      (node (ref "C6") (pin "2") (pinfunction "2_2") (pintype "passive"))
      (node (ref "C7") (pin "2") (pinfunction "2_2") (pintype "passive"))
      (node (ref "C8") (pin "2") (pinfunction "2_2") (pintype "passive"))
      (node (ref "C9") (pin "2") (pinfunction "2_2") (pintype "passive"))
      (node (ref "IC1") (pin "14") (pinfunction "GND_3_14") (pintype "bidirectional"))
      (node (ref "IC1") (pin "20") (pinfunction "GND_4_20") (pintype "bidirectional"))
      (node (ref "IC1") (pin "25") (pinfunction "GND_5_25") (pintype "bidirectional"))
      (node (ref "IC1") (pin "30") (pinfunction "GND_6_30") (pintype "bidirectional"))
      (node (ref "IC1") (pin "34") (pinfunction "GND_7_34") (pintype "bidirectional"))
      (node (ref "IC1") (pin "39") (pinfunction "GND_8_39") (pintype "bidirectional"))
      (node (ref "IC1") (pin "6") (pinfunction "GND_1_6") (pintype "bidirectional"))
      (node (ref "IC1") (pin "9") (pinfunction "GND_2_9") (pintype "bidirectional"))
      (node (ref "IC2") (pin "21") (pinfunction "GND_21") (pintype "power_in"))
      (node (ref "IC2") (pin "3") (pinfunction "GND_3") (pintype "power_in"))
      (node (ref "IC2") (pin "5") (pinfunction "GND_5") (pintype "power_in"))
      (node (ref "IC3") (pin "3") (pinfunction "GND_3") (pintype "power_in"))
      (node (ref "IC3") (pin "9") (pinfunction "THERM_9") (pintype "power_in"))
      (node (ref "IC4") (pin "2") (pinfunction "GND_2") (pintype "bidirectional"))
      (node (ref "IC5") (pin "4") (pinfunction "GND_4") (pintype "bidirectional"))
      (node (ref "J1") (pin "2") (pinfunction "2_2") (pintype "passive"))
      (node (ref "J1") (pin "3") (pinfunction "3_3") (pintype "passive"))
      (node (ref "J2") (pin "5") (pinfunction "5_5") (pintype "bidirectional"))
      (node (ref "J3") (pin "5") (pinfunction "5_5") (pintype "bidirectional"))
      (node (ref "J4") (pin "5") (pinfunction "5_5") (pintype "bidirectional"))
      (node (ref "J5") (pin "5") (pinfunction "5_5") (pintype "bidirectional"))
      (node (ref "J6") (pin "5") (pinfunction "5_5") (pintype "bidirectional"))
      (node (ref "JP1") (pin "1") (pinfunction "1_1") (pintype "passive"))
      (node (ref "JP2") (pin "2") (pinfunction "2_2") (pintype "passive"))
      (node (ref "LED1") (pin "2") (pinfunction "RED_CATHODE_2") (pintype "bidirectional"))
      (node (ref "LED1") (pin "4") (pinfunction "GREEN_CATHODE_4") (pintype "bidirectional"))
      (node (ref "LED1") (pin "6") (pinfunction "BLUE_CATHODE_6") (pintype "bidirectional"))
      (node (ref "R10") (pin "1") (pinfunction "1_1") (pintype "passive"))
      (node (ref "R12") (pin "2") (pinfunction "2_2") (pintype "passive"))
      (node (ref "R14") (pin "2") (pinfunction "2_2") (pintype "passive"))
      (node (ref "R19") (pin "2") (pinfunction "2_2") (pintype "passive"))
      (node (ref "R5") (pin "2") (pinfunction "2_2") (pintype "passive"))
      (node (ref "R6") (pin "2") (pinfunction "2_2") (pintype "passive"))
      (node (ref "R7") (pin "2") (pinfunction "2_2") (pintype "passive"))
      (node (ref "R8") (pin "1") (pinfunction "1_1") (pintype "passive"))
      (node (ref "S1") (pin "1") (pinfunction "S_1") (pintype "passive"))
      (node (ref "S1") (pin "2") (pinfunction "S1_2") (pintype "passive"))
      (node (ref "S2") (pin "1") (pinfunction "S_1") (pintype "passive"))
      (node (ref "S2") (pin "2") (pinfunction "S1_2") (pintype "passive"))
      (node (ref "T1") (pin "E") (pinfunction "E_E") (pintype "passive"))
      (node (ref "T2") (pin "E") (pinfunction "E_E") (pintype "passive"))
      (node (ref "U$1") (pin "17") (pinfunction "GND1_17") (pintype "power_in"))
      (node (ref "U$1") (pin "18") (pinfunction "GND2_18") (pintype "power_in"))
      (node (ref "U$1") (pin "19") (pinfunction "GND3_19") (pintype "power_in"))
      (node (ref "U$1") (pin "20") (pinfunction "GND4_20") (pintype "power_in"))
      (node (ref "U$2") (pin "17") (pinfunction "GND1_17") (pintype "power_in"))
      (node (ref "U$2") (pin "18") (pinfunction "GND2_18") (pintype "power_in"))
      (node (ref "U$2") (pin "19") (pinfunction "GND3_19") (pintype "power_in"))
      (node (ref "U$2") (pin "20") (pinfunction "GND4_20") (pintype "power_in"))
      (node (ref "U$3") (pin "17") (pinfunction "GND1_17") (pintype "power_in"))
      (node (ref "U$3") (pin "18") (pinfunction "GND2_18") (pintype "power_in"))
      (node (ref "U$3") (pin "19") (pinfunction "GND3_19") (pintype "power_in"))
      (node (ref "U$3") (pin "20") (pinfunction "GND4_20") (pintype "power_in"))
      (node (ref "U$4") (pin "17") (pinfunction "GND1_17") (pintype "power_in"))
      (node (ref "U$4") (pin "18") (pinfunction "GND2_18") (pintype "power_in"))
      (node (ref "U$4") (pin "19") (pinfunction "GND3_19") (pintype "power_in"))
      (node (ref "U$4") (pin "20") (pinfunction "GND4_20") (pintype "power_in"))
      (node (ref "U$5") (pin "17") (pinfunction "GND1_17") (pintype "power_in"))
      (node (ref "U$5") (pin "18") (pinfunction "GND2_18") (pintype "power_in"))
      (node (ref "U$5") (pin "19") (pinfunction "GND3_19") (pintype "power_in"))
      (node (ref "U$5") (pin "20") (pinfunction "GND4_20") (pintype "power_in"))
    )
    (net (code "44") (name "Net-(C17-Pad1)") (class "Default")
      (node (ref "C17") (pin "1") (pinfunction "1_1") (pintype "passive"))
      (node (ref "R15") (pin "1") (pinfunction "1_1") (pintype "passive"))
    )
    (net (code "45") (name "Net-(D1-A_1)") (class "Default")
      (node (ref "D1") (pin "1") (pinfunction "A_1_1") (pintype "bidirectional"))
      (node (ref "D1") (pin "2") (pinfunction "A_2_2") (pintype "bidirectional"))
      (node (ref "IC4") (pin "1") (pinfunction "SW_1") (pintype "bidirectional"))
      (node (ref "R15") (pin "2") (pinfunction "2_2") (pintype "passive"))
      (node (ref "U$6") (pin "P$2") (pinfunction "2_P$2") (pintype "passive"))
    )
    (net (code "46") (name "Net-(D1-K)") (class "Default")
      (node (ref "C16") (pin "1") (pinfunction "1_1") (pintype "passive"))
      (node (ref "C17") (pin "2") (pinfunction "2_2") (pintype "passive"))
      (node (ref "D1") (pin "3") (pinfunction "K_3") (pintype "bidirectional"))
      (node (ref "IC4") (pin "4") (pinfunction "VOUT_4") (pintype "bidirectional"))
      (node (ref "U$8") (pin "P$1") (pinfunction "1_P$1") (pintype "passive"))
    )
    (net (code "47") (name "Net-(IC1-GPIO5{slash}{slash}GPCLK1)") (class "Default")
      (node (ref "IC1") (pin "29") (pinfunction "GPIO5//GPCLK1_29") (pintype "bidirectional"))
      (node (ref "R32") (pin "2") (pinfunction "2_2") (pintype "passive"))
    )
    (net (code "48") (name "Net-(IC1-GPIO12{slash}PWM0)") (class "Default")
      (node (ref "IC1") (pin "32") (pinfunction "GPIO12/PWM0_32") (pintype "bidirectional"))
      (node (ref "R37") (pin "2") (pinfunction "2_2") (pintype "passive"))
    )
    (net (code "49") (name "Net-(IC1-GPIO13{slash}PWM1)") (class "Default")
      (node (ref "IC1") (pin "33") (pinfunction "GPIO13/PWM1_33") (pintype "bidirectional"))
      (node (ref "R36") (pin "2") (pinfunction "2_2") (pintype "passive"))
    )
    (net (code "50") (name "Net-(IC1-GPIO16{slash}SPI1_CS2)") (class "Default")
      (node (ref "IC1") (pin "36") (pinfunction "GPIO16/SPI1_CS2_36") (pintype "bidirectional"))
      (node (ref "R34") (pin "2") (pinfunction "2_2") (pintype "passive"))
    )
    (net (code "51") (name "Net-(IC1-GPIO19{slash}SPI0_MISO1{slash}PWM1)") (class "Default")
      (node (ref "IC1") (pin "35") (pinfunction "GPIO19/SPI0_MISO1/PWM1_35") (pintype "bidirectional"))
      (node (ref "R35") (pin "2") (pinfunction "2_2") (pintype "passive"))
    )
    (net (code "52") (name "Net-(IC1-GPIO21{slash}SPI0_SCLK1)") (class "Default")
      (node (ref "IC1") (pin "40") (pinfunction "GPIO21/SPI0_SCLK1_40") (pintype "bidirectional"))
      (node (ref "S2") (pin "3") (pinfunction "P_3") (pintype "passive"))
      (node (ref "S2") (pin "4") (pinfunction "P1_4") (pintype "passive"))
    )
    (net (code "53") (name "Net-(IC1-GPIO26)") (class "Default")
      (node (ref "IC1") (pin "37") (pinfunction "GPIO26_37") (pintype "bidirectional"))
      (node (ref "R33") (pin "2") (pinfunction "2_2") (pintype "passive"))
    )
    (net (code "54") (name "Net-(IC1-GPIO27)") (class "Default")
      (node (ref "IC1") (pin "13") (pinfunction "GPIO27_13") (pintype "bidirectional"))
      (node (ref "R25") (pin "1") (pinfunction "1_1") (pintype "passive"))
    )
    (net (code "55") (name "Net-(IC1-GPIO_18{slash}PWM0{slash}SPI1_CS0)") (class "Default")
      (node (ref "IC1") (pin "12") (pinfunction "GPIO_18/PWM0/SPI1_CS0_12") (pintype "bidirectional"))
      (node (ref "R26") (pin "1") (pinfunction "1_1") (pintype "passive"))
    )
    (net (code "56") (name "Net-(IC1-GPIO_22)") (class "Default")
      (node (ref "IC1") (pin "15") (pinfunction "GPIO_22_15") (pintype "bidirectional"))
      (node (ref "R24") (pin "1") (pinfunction "1_1") (pintype "passive"))
    )
    (net (code "57") (name "Net-(IC1-GPIO_23)") (class "Default")
      (node (ref "IC1") (pin "16") (pinfunction "GPIO_23_16") (pintype "bidirectional"))
      (node (ref "R23") (pin "1") (pinfunction "1_1") (pintype "passive"))
    )
    (net (code "58") (name "Net-(IC1-GPIO_24)") (class "Default")
      (node (ref "IC1") (pin "18") (pinfunction "GPIO_24_18") (pintype "bidirectional"))
      (node (ref "R22") (pin "1") (pinfunction "1_1") (pintype "passive"))
    )
    (net (code "59") (name "Net-(IC2-AREF)") (class "Default")
      (node (ref "C11") (pin "2") (pinfunction "2_2") (pintype "passive"))
      (node (ref "IC2") (pin "20") (pinfunction "AREF_20") (pintype "passive"))
    )
    (net (code "60") (name "Net-(IC2-PB1(OC1A))") (class "Default")
      (node (ref "IC2") (pin "13") (pinfunction "PB1(OC1A)_13") (pintype "bidirectional"))
      (node (ref "R28") (pin "1") (pinfunction "1_1") (pintype "passive"))
    )
    (net (code "61") (name "Net-(IC2-PB4(MISO))") (class "Default")
      (node (ref "IC2") (pin "16") (pinfunction "PB4(MISO)_16") (pintype "bidirectional"))
      (node (ref "R30") (pin "1") (pinfunction "1_1") (pintype "passive"))
    )
    (net (code "62") (name "Net-(IC2-PB6(XTAL1{slash}TOSC1))") (class "Default")
      (node (ref "IC2") (pin "7") (pinfunction "PB6(XTAL1/TOSC1)_7") (pintype "bidirectional"))
      (node (ref "Q1") (pin "2") (pinfunction "2_2") (pintype "passive"))
    )
    (net (code "63") (name "Net-(IC2-PB7(XTAL2{slash}TOSC2))") (class "Default")
      (node (ref "IC2") (pin "8") (pinfunction "PB7(XTAL2/TOSC2)_8") (pintype "bidirectional"))
      (node (ref "Q1") (pin "1") (pinfunction "1_1") (pintype "passive"))
    )
    (net (code "64") (name "Net-(IC2-PC6({slash}RESET))") (class "Default")
      (node (ref "IC2") (pin "29") (pinfunction "PC6(/RESET)_29") (pintype "bidirectional"))
      (node (ref "R1") (pin "2") (pinfunction "2_2") (pintype "passive"))
    )
    (net (code "65") (name "Net-(IC5-BST)") (class "Default")
      (node (ref "C21") (pin "2") (pinfunction "2_2") (pintype "passive"))
      (node (ref "IC5") (pin "6") (pinfunction "BST_6") (pintype "bidirectional"))
    )
    (net (code "66") (name "Net-(IC5-EN)") (class "Default")
      (node (ref "IC5") (pin "2") (pinfunction "EN_2") (pintype "bidirectional"))
      (node (ref "IC5") (pin "3") (pinfunction "VIN_3") (pintype "bidirectional"))
      (node (ref "U$11") (pin "2") (pinfunction "C_2") (pintype "passive"))
    )
    (net (code "67") (name "Net-(IC5-SW)") (class "Default")
      (node (ref "C21") (pin "1") (pinfunction "1_1") (pintype "passive"))
      (node (ref "IC5") (pin "5") (pinfunction "SW_5") (pintype "bidirectional"))
      (node (ref "L1") (pin "1") (pinfunction "1_1") (pintype "bidirectional"))
    )
    (net (code "68") (name "Net-(LED1-BLUE_ANODE)") (class "Default")
      (node (ref "LED1") (pin "5") (pinfunction "BLUE_ANODE_5") (pintype "bidirectional"))
      (node (ref "R40") (pin "1") (pinfunction "1_1") (pintype "passive"))
    )
    (net (code "69") (name "Net-(LED1-GREEN_ANODE)") (class "Default")
      (node (ref "LED1") (pin "3") (pinfunction "GREEN_ANODE_3") (pintype "bidirectional"))
      (node (ref "R39") (pin "1") (pinfunction "1_1") (pintype "passive"))
    )
    (net (code "70") (name "Net-(LED1-RED_ANODE)") (class "Default")
      (node (ref "LED1") (pin "1") (pinfunction "RED_ANODE_1") (pintype "bidirectional"))
      (node (ref "R38") (pin "1") (pinfunction "1_1") (pintype "passive"))
    )
    (net (code "71") (name "Net-(Q2-D)") (class "Default")
      (node (ref "Q2") (pin "2") (pinfunction "D_2") (pintype "bidirectional"))
      (node (ref "Q2") (pin "4") (pinfunction "D_TAB_4") (pintype "bidirectional"))
      (node (ref "U$10") (pin "1") (pinfunction "A_1") (pintype "passive"))
    )
    (net (code "72") (name "Net-(Q2-G)") (class "Default")
      (node (ref "Q2") (pin "1") (pinfunction "G_1") (pintype "bidirectional"))
      (node (ref "R16") (pin "2") (pinfunction "2_2") (pintype "passive"))
      (node (ref "T1") (pin "C") (pinfunction "C_C") (pintype "passive"))
      (node (ref "U$12") (pin "1") (pinfunction "A_1") (pintype "passive"))
    )
    (net (code "73") (name "Net-(R17-Pad1)") (class "Default")
      (node (ref "R17") (pin "1") (pinfunction "1_1") (pintype "passive"))
      (node (ref "T1") (pin "B") (pinfunction "B_B") (pintype "passive"))
    )
    (net (code "74") (name "Net-(R30-Pad2)") (class "Default")
      (node (ref "R30") (pin "2") (pinfunction "2_2") (pintype "passive"))
      (node (ref "T2") (pin "B") (pinfunction "B_B") (pintype "passive"))
    )
    (net (code "75") (name "Net-(U$10-C)") (class "Default")
      (node (ref "C18") (pin "1") (pinfunction "1_1") (pintype "passive"))
      (node (ref "U$10") (pin "2") (pinfunction "C_2") (pintype "passive"))
      (node (ref "U$6") (pin "P$1") (pinfunction "1_P$1") (pintype "passive"))
      (node (ref "U$9") (pin "2") (pinfunction "C_2") (pintype "passive"))
    )
    (net (code "76") (name "unconnected-(IC1-DNC_1-Pad27)") (class "Default")
      (node (ref "IC1") (pin "27") (pinfunction "DNC_1_27") (pintype "bidirectional"))
    )
    (net (code "77") (name "unconnected-(IC1-DNC_2-Pad28)") (class "Default")
      (node (ref "IC1") (pin "28") (pinfunction "DNC_2_28") (pintype "bidirectional"))
    )
    (net (code "78") (name "unconnected-(IC1-GPIO20{slash}SPI0_MOSI1-Pad38)") (class "Default")
      (node (ref "IC1") (pin "38") (pinfunction "GPIO20/SPI0_MOSI1_38") (pintype "bidirectional"))
    )
    (net (code "79") (name "unconnected-(IC1-GPIO_7{slash}SPI0_CE2_N-Pad26)") (class "Default")
      (node (ref "IC1") (pin "26") (pinfunction "GPIO_7/SPI0_CE2_N_26") (pintype "bidirectional"))
    )
    (net (code "80") (name "unconnected-(IC1-GPIO_8{slash}SPI0_CE1_N-Pad24)") (class "Default")
      (node (ref "IC1") (pin "24") (pinfunction "GPIO_8/SPI0_CE1_N_24") (pintype "bidirectional"))
    )
    (net (code "81") (name "unconnected-(IC1-GPIO_14{slash}[UART]_TXD0-Pad8)") (class "Default")
      (node (ref "IC1") (pin "8") (pinfunction "GPIO_14/[UART]_TXD0_8") (pintype "bidirectional"))
    )
    (net (code "82") (name "unconnected-(IC1-GPIO_15{slash}[UART]_RXD0-Pad10)") (class "Default")
      (node (ref "IC1") (pin "10") (pinfunction "GPIO_15/[UART]_RXD0_10") (pintype "bidirectional"))
    )
    (net (code "83") (name "unconnected-(IC1-GPIO_17{slash}SPI1_CS1-Pad11)") (class "Default")
      (node (ref "IC1") (pin "11") (pinfunction "GPIO_17/SPI1_CS1_11") (pintype "bidirectional"))
    )
    (net (code "84") (name "unconnected-(IC1-GPIO_25-Pad22)") (class "Default")
      (node (ref "IC1") (pin "22") (pinfunction "GPIO_25_22") (pintype "bidirectional"))
    )
    (net (code "85") (name "unconnected-(IC1-RUN_2-Pad42)") (class "Default")
      (node (ref "IC1") (pin "42") (pinfunction "RUN_2_42") (pintype "bidirectional"))
    )
    (net (code "86") (name "unconnected-(IC1-TV_+-Pad43)") (class "Default")
      (node (ref "IC1") (pin "43") (pinfunction "TV_+_43") (pintype "bidirectional"))
    )
    (net (code "87") (name "unconnected-(IC1-TV_--Pad44)") (class "Default")
      (node (ref "IC1") (pin "44") (pinfunction "TV_-_44") (pintype "bidirectional"))
    )
    (net (code "88") (name "unconnected-(IC2-ADC6-Pad19)") (class "Default")
      (node (ref "IC2") (pin "19") (pinfunction "ADC6_19") (pintype "bidirectional"))
    )
    (net (code "89") (name "unconnected-(IC2-ADC7-Pad22)") (class "Default")
      (node (ref "IC2") (pin "22") (pinfunction "ADC7_22") (pintype "bidirectional"))
    )
    (net (code "90") (name "unconnected-(IC2-PD0(RXD)-Pad30)") (class "Default")
      (node (ref "IC2") (pin "30") (pinfunction "PD0(RXD)_30") (pintype "bidirectional"))
    )
    (net (code "91") (name "unconnected-(IC2-PD1(TXD)-Pad31)") (class "Default")
      (node (ref "IC2") (pin "31") (pinfunction "PD1(TXD)_31") (pintype "bidirectional"))
    )
    (net (code "92") (name "unconnected-(IC4-NC_1-Pad3)") (class "Default")
      (node (ref "IC4") (pin "3") (pinfunction "NC_1_3") (pintype "bidirectional"))
    )
    (net (code "93") (name "unconnected-(IC4-NC_2-Pad5)") (class "Default")
      (node (ref "IC4") (pin "5") (pinfunction "NC_2_5") (pintype "bidirectional"))
    )
  )
)
